# PentaFnord_LedBar_0_91r.net
KiCad netlist of a schematic drawn in EAGLE
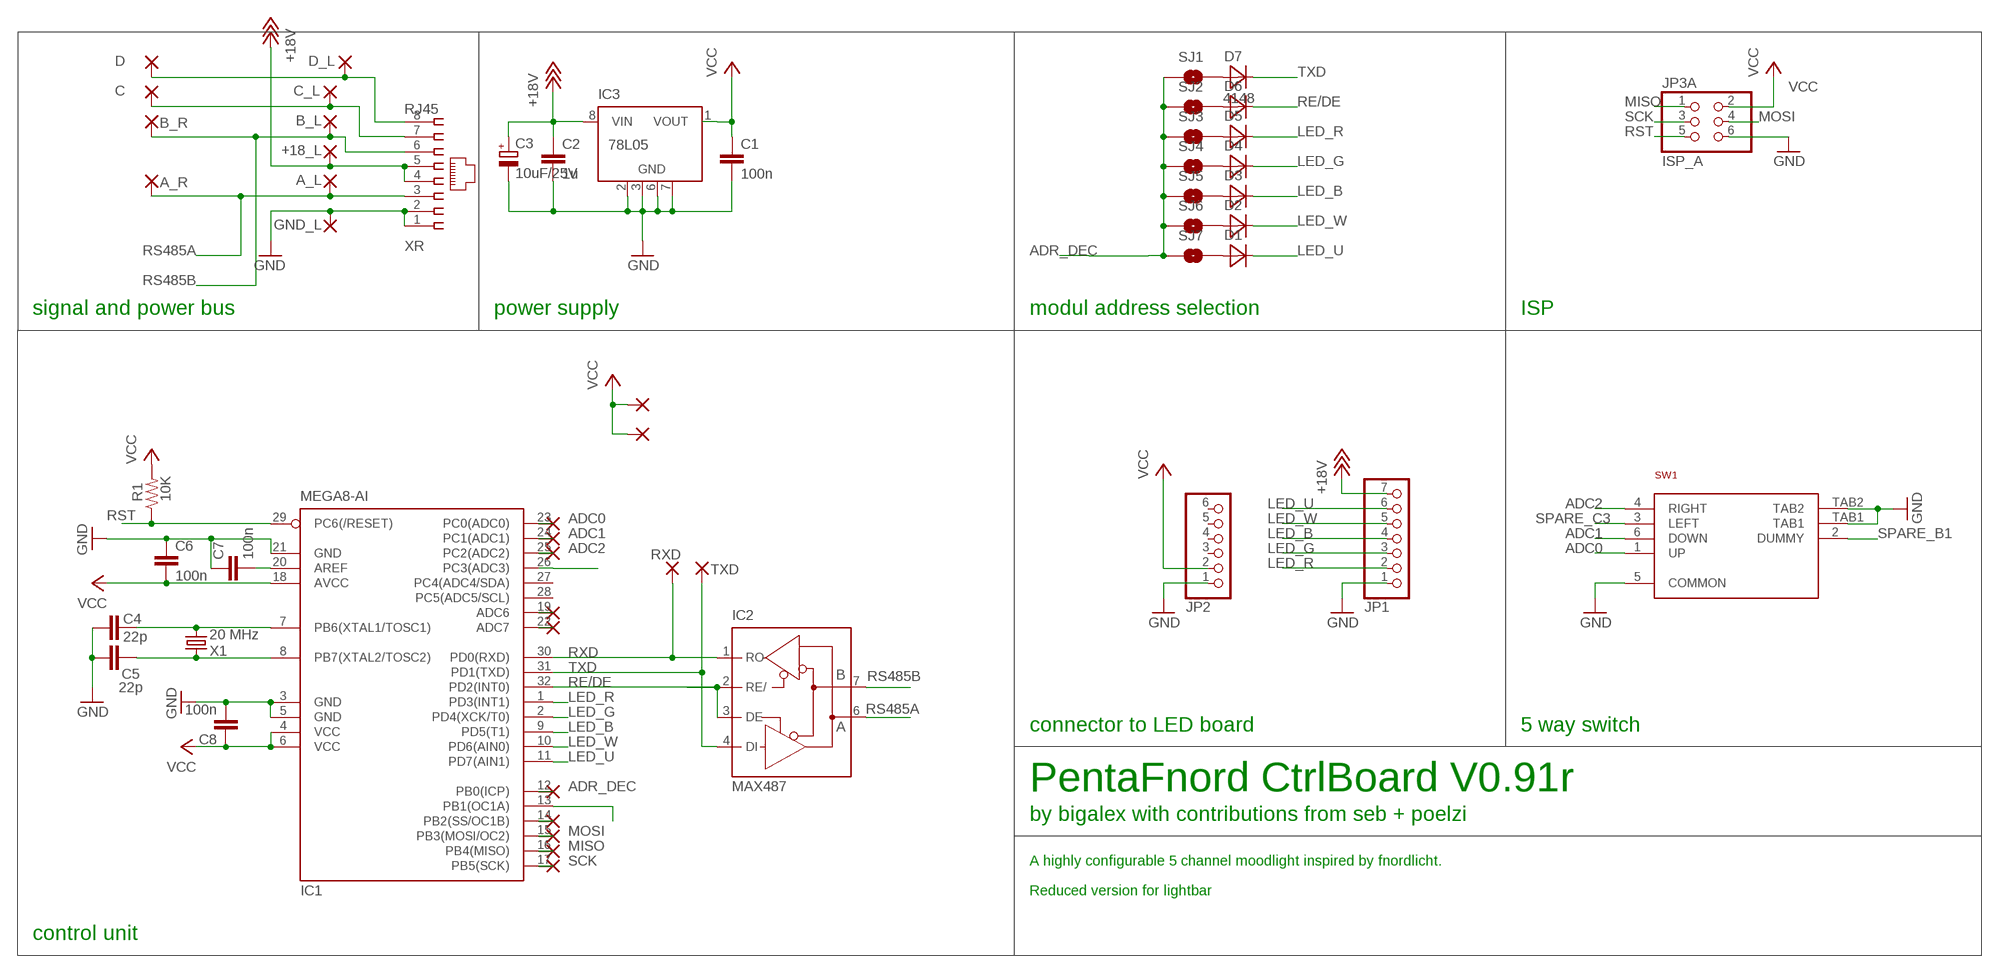
[diagram p0: schematic, sheet 1]
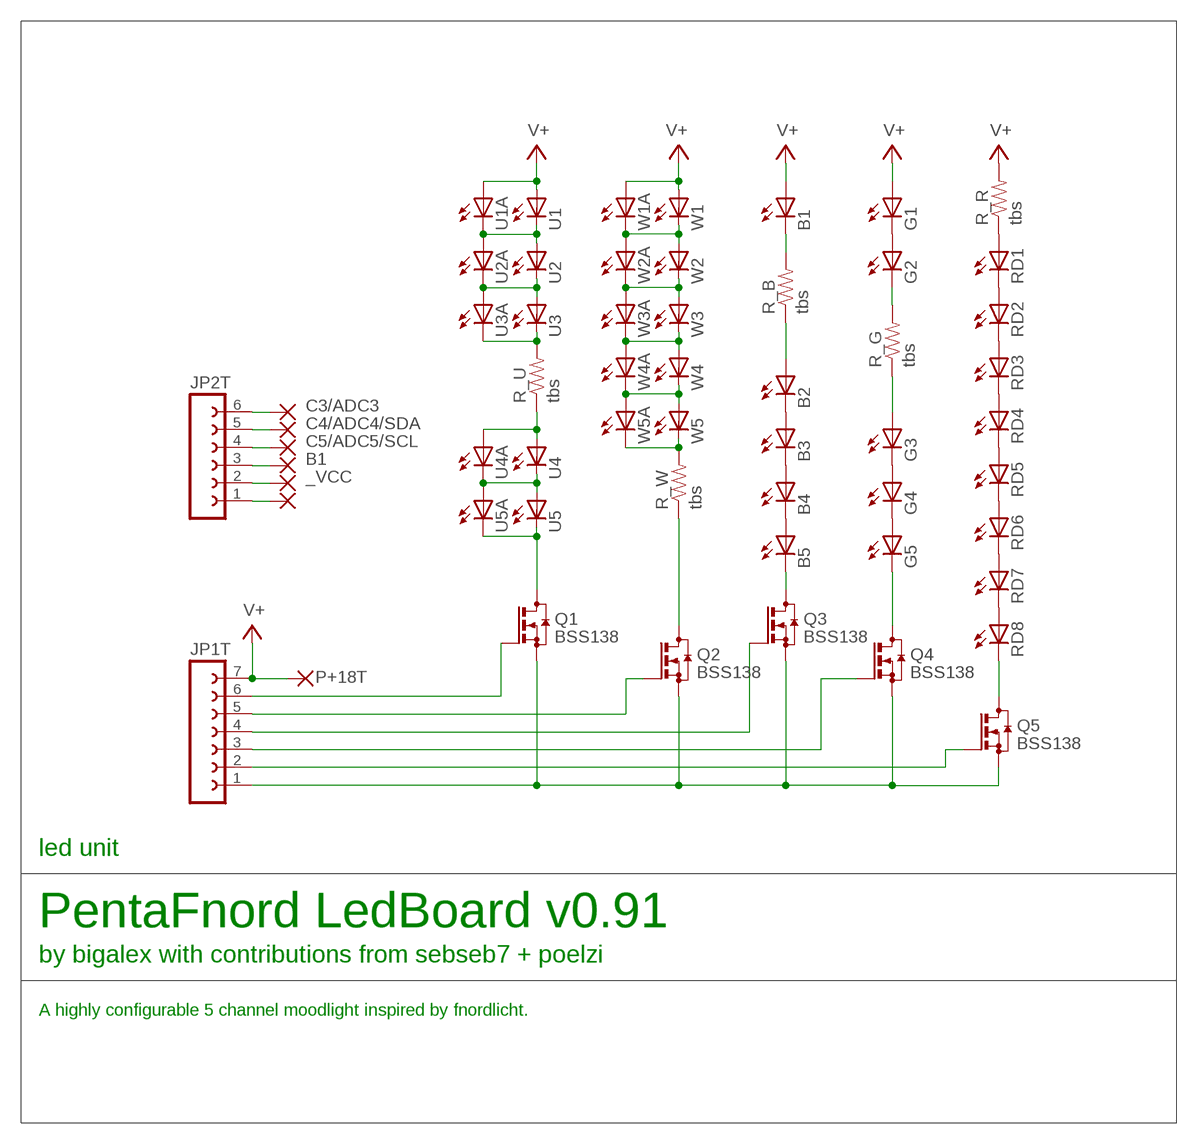
[diagram p1: schematic, sheet 2]

(export (version "E")
  (design (tool "Eeschema 10.0.6"))
  (components
    (comp (ref "B1")
      (value "LED5MM")
      (footprint "eagle-import:LED5MM")
      (libsource (lib "eagle-import") (part "LED5MM"))
    )
    (comp (ref "B2")
      (value "LED5MM")
      (footprint "eagle-import:LED5MM")
      (libsource (lib "eagle-import") (part "LED5MM"))
    )
    (comp (ref "B3")
      (value "LED5MM")
      (footprint "eagle-import:LED5MM")
      (libsource (lib "eagle-import") (part "LED5MM"))
    )
    (comp (ref "B4")
      (value "LED5MM")
      (footprint "eagle-import:LED5MM")
      (libsource (lib "eagle-import") (part "LED5MM"))
    )
    (comp (ref "B5")
      (value "LED5MM")
      (footprint "eagle-import:LED5MM")
      (libsource (lib "eagle-import") (part "LED5MM"))
    )
    (comp (ref "G1")
      (value "LED5MM")
      (footprint "eagle-import:LED5MM")
      (libsource (lib "eagle-import") (part "LED5MM"))
    )
    (comp (ref "G2")
      (value "LED5MM")
      (footprint "eagle-import:LED5MM")
      (libsource (lib "eagle-import") (part "LED5MM"))
    )
    (comp (ref "G3")
      (value "LED5MM")
      (footprint "eagle-import:LED5MM")
      (libsource (lib "eagle-import") (part "LED5MM"))
    )
    (comp (ref "G4")
      (value "LED5MM")
      (footprint "eagle-import:LED5MM")
      (libsource (lib "eagle-import") (part "LED5MM"))
    )
    (comp (ref "G5")
      (value "LED5MM")
      (footprint "eagle-import:LED5MM")
      (libsource (lib "eagle-import") (part "LED5MM"))
    )
    (comp (ref "JP1T")
      (value "FE07-1")
      (footprint "eagle-import:FE07")
      (libsource (lib "eagle-import") (part "FE07-1"))
    )
    (comp (ref "JP2T")
      (value "FE06-1")
      (footprint "eagle-import:FE06")
      (libsource (lib "eagle-import") (part "FE06-1"))
    )
    (comp (ref "P+5T")
      (value "WIREPAD2,54/0,8")
      (footprint "eagle-import:2,54_0,8")
      (libsource (lib "eagle-import") (part "WIREPAD2,54/0,8"))
    )
    (comp (ref "P+18T")
      (value "WIREPAD2,54/0,8")
      (footprint "eagle-import:2,54_0,8")
      (libsource (lib "eagle-import") (part "WIREPAD2,54/0,8"))
    )
    (comp (ref "PB1T")
      (value "WIREPAD2,54/0,8")
      (footprint "eagle-import:2,54_0,8")
      (libsource (lib "eagle-import") (part "WIREPAD2,54/0,8"))
    )
    (comp (ref "PC3T")
      (value "WIREPAD2,54/0,8")
      (footprint "eagle-import:2,54_0,8")
      (libsource (lib "eagle-import") (part "WIREPAD2,54/0,8"))
    )
    (comp (ref "PC4T")
      (value "WIREPAD2,54/0,8")
      (footprint "eagle-import:2,54_0,8")
      (libsource (lib "eagle-import") (part "WIREPAD2,54/0,8"))
    )
    (comp (ref "PC5T")
      (value "WIREPAD2,54/0,8")
      (footprint "eagle-import:2,54_0,8")
      (libsource (lib "eagle-import") (part "WIREPAD2,54/0,8"))
    )
    (comp (ref "PGNDT1")
      (value "WIREPAD2,54/0,8")
      (footprint "eagle-import:2,54_0,8")
      (libsource (lib "eagle-import") (part "WIREPAD2,54/0,8"))
    )
    (comp (ref "Q1")
      (value "BSS138")
      (footprint "eagle-import:SOT23")
      (libsource (lib "eagle-import") (part "BSS123"))
    )
    (comp (ref "Q2")
      (value "BSS138")
      (footprint "eagle-import:SOT23")
      (libsource (lib "eagle-import") (part "BSS123"))
    )
    (comp (ref "Q3")
      (value "BSS138")
      (footprint "eagle-import:SOT23")
      (libsource (lib "eagle-import") (part "BSS123"))
    )
    (comp (ref "Q4")
      (value "BSS138")
      (footprint "eagle-import:SOT23")
      (libsource (lib "eagle-import") (part "BSS123"))
    )
    (comp (ref "Q5")
      (value "BSS138")
      (footprint "eagle-import:SOT23")
      (libsource (lib "eagle-import") (part "BSS123"))
    )
    (comp (ref "RD1")
      (value "LED5MM")
      (footprint "eagle-import:LED5MM")
      (libsource (lib "eagle-import") (part "LED5MM"))
    )
    (comp (ref "RD2")
      (value "LED5MM")
      (footprint "eagle-import:LED5MM")
      (libsource (lib "eagle-import") (part "LED5MM"))
    )
    (comp (ref "RD3")
      (value "LED5MM")
      (footprint "eagle-import:LED5MM")
      (libsource (lib "eagle-import") (part "LED5MM"))
    )
    (comp (ref "RD4")
      (value "LED5MM")
      (footprint "eagle-import:LED5MM")
      (libsource (lib "eagle-import") (part "LED5MM"))
    )
    (comp (ref "RD5")
      (value "LED5MM")
      (footprint "eagle-import:LED5MM")
      (libsource (lib "eagle-import") (part "LED5MM"))
    )
    (comp (ref "RD6")
      (value "LED5MM")
      (footprint "eagle-import:LED5MM")
      (libsource (lib "eagle-import") (part "LED5MM"))
    )
    (comp (ref "RD7")
      (value "LED5MM")
      (footprint "eagle-import:LED5MM")
      (libsource (lib "eagle-import") (part "LED5MM"))
    )
    (comp (ref "RD8")
      (value "LED5MM")
      (footprint "eagle-import:LED5MM")
      (libsource (lib "eagle-import") (part "LED5MM"))
    )
    (comp (ref "R_B")
      (value "tbs")
      (footprint "eagle-import:1206")
      (libsource (lib "eagle-import") (part "RESISTOR1206"))
    )
    (comp (ref "R_G")
      (value "tbs")
      (footprint "eagle-import:1206")
      (libsource (lib "eagle-import") (part "RESISTOR1206"))
    )
    (comp (ref "R_R")
      (value "tbs")
      (footprint "eagle-import:1206")
      (libsource (lib "eagle-import") (part "RESISTOR1206"))
    )
    (comp (ref "R_U")
      (value "tbs")
      (footprint "eagle-import:1206")
      (libsource (lib "eagle-import") (part "RESISTOR1206"))
    )
    (comp (ref "R_W")
      (value "tbs")
      (footprint "eagle-import:1206")
      (libsource (lib "eagle-import") (part "RESISTOR1206"))
    )
    (comp (ref "U1")
      (value "NICHIA_NSSL157T-H3")
      (footprint "eagle-import:PLCC2")
      (libsource (lib "eagle-import") (part "LED_PLCC2"))
    )
    (comp (ref "U1A")
      (value "LED5MM")
      (footprint "eagle-import:LED5MM")
      (libsource (lib "eagle-import") (part "LED5MM"))
    )
    (comp (ref "U2")
      (value "NICHIA_NSSL157T-H3")
      (footprint "eagle-import:PLCC2")
      (libsource (lib "eagle-import") (part "LED_PLCC2"))
    )
    (comp (ref "U2A")
      (value "LED5MM")
      (footprint "eagle-import:LED5MM")
      (libsource (lib "eagle-import") (part "LED5MM"))
    )
    (comp (ref "U3")
      (value "NICHIA_NSSL157T-H3")
      (footprint "eagle-import:PLCC2")
      (libsource (lib "eagle-import") (part "LED_PLCC2"))
    )
    (comp (ref "U3A")
      (value "LED5MM")
      (footprint "eagle-import:LED5MM")
      (libsource (lib "eagle-import") (part "LED5MM"))
    )
    (comp (ref "U4")
      (value "NICHIA_NSSL157T-H3")
      (footprint "eagle-import:PLCC2")
      (libsource (lib "eagle-import") (part "LED_PLCC2"))
    )
    (comp (ref "U4A")
      (value "LED5MM")
      (footprint "eagle-import:LED5MM")
      (libsource (lib "eagle-import") (part "LED5MM"))
    )
    (comp (ref "U5")
      (value "NICHIA_NSSL157T-H3")
      (footprint "eagle-import:PLCC2")
      (libsource (lib "eagle-import") (part "LED_PLCC2"))
    )
    (comp (ref "U5A")
      (value "LED5MM")
      (footprint "eagle-import:LED5MM")
      (libsource (lib "eagle-import") (part "LED5MM"))
    )
    (comp (ref "W1")
      (value "NICHIA_NSSL157T-H3")
      (footprint "eagle-import:NICHIA_NSSL157T-H3")
      (libsource (lib "eagle-import") (part "NICHIA_NSSL157T-H3"))
    )
    (comp (ref "W1A")
      (value "LED5MM")
      (footprint "eagle-import:LED5MM")
      (libsource (lib "eagle-import") (part "LED5MM"))
    )
    (comp (ref "W2")
      (value "NICHIA_NSSL157T-H3")
      (footprint "eagle-import:NICHIA_NSSL157T-H3")
      (libsource (lib "eagle-import") (part "NICHIA_NSSL157T-H3"))
    )
    (comp (ref "W2A")
      (value "LED5MM")
      (footprint "eagle-import:LED5MM")
      (libsource (lib "eagle-import") (part "LED5MM"))
    )
    (comp (ref "W3")
      (value "NICHIA_NSSL157T-H3")
      (footprint "eagle-import:NICHIA_NSSL157T-H3")
      (libsource (lib "eagle-import") (part "NICHIA_NSSL157T-H3"))
    )
    (comp (ref "W3A")
      (value "LED5MM")
      (footprint "eagle-import:LED5MM")
      (libsource (lib "eagle-import") (part "LED5MM"))
    )
    (comp (ref "W4")
      (value "NICHIA_NSSL157T-H3")
      (footprint "eagle-import:NICHIA_NSSL157T-H3")
      (libsource (lib "eagle-import") (part "NICHIA_NSSL157T-H3"))
    )
    (comp (ref "W4A")
      (value "LED5MM")
      (footprint "eagle-import:LED5MM")
      (libsource (lib "eagle-import") (part "LED5MM"))
    )
    (comp (ref "W5")
      (value "NICHIA_NSSL157T-H3")
      (footprint "eagle-import:NICHIA_NSSL157T-H3")
      (libsource (lib "eagle-import") (part "NICHIA_NSSL157T-H3"))
    )
    (comp (ref "W5A")
      (value "LED5MM")
      (footprint "eagle-import:LED5MM")
      (libsource (lib "eagle-import") (part "LED5MM"))
    )
    (comp (ref "+18_L")
      (value "WIREPADSMD2,54-5,08")
      (footprint "eagle-import:SMD2,54-5,08")
      (libsource (lib "eagle-import") (part "WIREPADSMD2,54-5,08"))
    )
    (comp (ref "ADC6")
      (value "WIREPADSMD1,27-254")
      (footprint "eagle-import:SMD1,27-2,54")
      (libsource (lib "eagle-import") (part "WIREPADSMD1,27-254"))
    )
    (comp (ref "ADC7")
      (value "WIREPADSMD1,27-254")
      (footprint "eagle-import:SMD1,27-2,54")
      (libsource (lib "eagle-import") (part "WIREPADSMD1,27-254"))
    )
    (comp (ref "A_L")
      (value "WIREPADSMD2,54-5,08")
      (footprint "eagle-import:SMD2,54-5,08")
      (libsource (lib "eagle-import") (part "WIREPADSMD2,54-5,08"))
    )
    (comp (ref "A_R")
      (value "WIREPADSMD1,27-254")
      (footprint "eagle-import:SMD1,27-2,54")
      (libsource (lib "eagle-import") (part "WIREPADSMD1,27-254"))
    )
    (comp (ref "B_L")
      (value "WIREPADSMD2,54-5,08")
      (footprint "eagle-import:SMD2,54-5,08")
      (libsource (lib "eagle-import") (part "WIREPADSMD2,54-5,08"))
    )
    (comp (ref "B_R")
      (value "WIREPADSMD1,27-254")
      (footprint "eagle-import:SMD1,27-2,54")
      (libsource (lib "eagle-import") (part "WIREPADSMD1,27-254"))
    )
    (comp (ref "C")
      (value "WIREPADSMD1,27-254")
      (footprint "eagle-import:SMD1,27-2,54")
      (libsource (lib "eagle-import") (part "WIREPADSMD1,27-254"))
    )
    (comp (ref "C1")
      (value "100n")
      (footprint "eagle-import:0805")
      (libsource (lib "eagle-import") (part "CAP0805"))
    )
    (comp (ref "C2")
      (value "1u")
      (footprint "eagle-import:0805")
      (libsource (lib "eagle-import") (part "CAP0805"))
    )
    (comp (ref "C3")
      (value "10uF/25V")
      (footprint "eagle-import:SMC_D")
      (libsource (lib "eagle-import") (part "CPOL-EUSMCD"))
    )
    (comp (ref "C4")
      (value "22p")
      (footprint "eagle-import:0805")
      (libsource (lib "eagle-import") (part "CAP0805"))
    )
    (comp (ref "C5")
      (value "22p")
      (footprint "eagle-import:0805")
      (libsource (lib "eagle-import") (part "CAP0805"))
    )
    (comp (ref "C6")
      (value "100n")
      (footprint "eagle-import:0805")
      (libsource (lib "eagle-import") (part "CAP0805"))
    )
    (comp (ref "C7")
      (value "100n")
      (footprint "eagle-import:0805")
      (libsource (lib "eagle-import") (part "CAP0805"))
    )
    (comp (ref "C8")
      (value "100n")
      (footprint "eagle-import:0805")
      (libsource (lib "eagle-import") (part "CAP0805"))
    )
    (comp (ref "C_L")
      (value "WIREPADSMD2,54-5,08")
      (footprint "eagle-import:SMD2,54-5,08")
      (libsource (lib "eagle-import") (part "WIREPADSMD2,54-5,08"))
    )
    (comp (ref "D")
      (value "WIREPADSMD1,27-254")
      (footprint "eagle-import:SMD1,27-2,54")
      (libsource (lib "eagle-import") (part "WIREPADSMD1,27-254"))
    )
    (comp (ref "D1")
      (value "DIODE_0805")
      (footprint "eagle-import:DIODE_0805")
      (libsource (lib "eagle-import") (part "DIODE_0805"))
    )
    (comp (ref "D2")
      (value "DIODE_0805")
      (footprint "eagle-import:DIODE_0805")
      (libsource (lib "eagle-import") (part "DIODE_0805"))
    )
    (comp (ref "D3")
      (value "DIODE_0805")
      (footprint "eagle-import:DIODE_0805")
      (libsource (lib "eagle-import") (part "DIODE_0805"))
    )
    (comp (ref "D4")
      (value "DIODE_0805")
      (footprint "eagle-import:DIODE_0805")
      (libsource (lib "eagle-import") (part "DIODE_0805"))
    )
    (comp (ref "D5")
      (value "DIODE_0805")
      (footprint "eagle-import:DIODE_0805")
      (libsource (lib "eagle-import") (part "DIODE_0805"))
    )
    (comp (ref "D6")
      (value "DIODE_0805")
      (footprint "eagle-import:DIODE_0805")
      (libsource (lib "eagle-import") (part "DIODE_0805"))
    )
    (comp (ref "D7")
      (value "4148")
      (footprint "eagle-import:DIODE_0805")
      (libsource (lib "eagle-import") (part "DIODE_0805"))
    )
    (comp (ref "D_L")
      (value "WIREPADSMD2,54-5,08")
      (footprint "eagle-import:SMD2,54-5,08")
      (libsource (lib "eagle-import") (part "WIREPADSMD2,54-5,08"))
    )
    (comp (ref "GND_L")
      (value "WIREPADSMD2,54-5,08")
      (footprint "eagle-import:SMD2,54-5,08")
      (libsource (lib "eagle-import") (part "WIREPADSMD2,54-5,08"))
    )
    (comp (ref "IC1")
      (value "MEGA8-AI")
      (footprint "eagle-import:TQFP32-08")
      (fields (field (name "MPN") "ATMEGA8-16AU"))
      (libsource (lib "eagle-import") (part "MEGA8-AI"))
    )
    (comp (ref "IC2")
      (value "MAX487")
      (footprint "eagle-import:SO08")
      (fields (field (name "MF") "MAXIM"))
      (libsource (lib "eagle-import") (part "MAX487"))
    )
    (comp (ref "IC3")
      (value "78L05")
      (footprint "eagle-import:SO08")
      (libsource (lib "eagle-import") (part "78LSMD05"))
    )
    (comp (ref "JP1")
      (value "PINHD-1X07_2.54-SMD-REVERSE")
      (footprint "eagle-import:1X07SMD-REVERSE")
      (libsource (lib "eagle-import") (part "PINHD-1X07_2.54-SMD-REVERSE"))
    )
    (comp (ref "JP2")
      (value "PINHD-1X06_2.54-SMD")
      (footprint "eagle-import:1X06SMD")
      (libsource (lib "eagle-import") (part "PINHD-1X06_2.54-SMD"))
    )
    (comp (ref "JP3A")
      (value "ISP_A")
      (footprint "eagle-import:2X03SMD")
      (libsource (lib "eagle-import") (part "PINHD-2X03_2.54-SMD"))
    )
    (comp (ref "PAD3")
      (value "WIREPADSMD1,27-254")
      (footprint "eagle-import:SMD1,27-2,54")
      (libsource (lib "eagle-import") (part "WIREPADSMD1,27-254"))
    )
    (comp (ref "PAD4")
      (value "WIREPADSMD1,27-254")
      (footprint "eagle-import:SMD1,27-2,54")
      (libsource (lib "eagle-import") (part "WIREPADSMD1,27-254"))
    )
    (comp (ref "PB0")
      (value "WIREPADSMD1,27-254")
      (footprint "eagle-import:SMD1,27-2,54")
      (libsource (lib "eagle-import") (part "WIREPADSMD1,27-254"))
    )
    (comp (ref "PB2")
      (value "WIREPADSMD1,27-254")
      (footprint "eagle-import:SMD1,27-2,54")
      (libsource (lib "eagle-import") (part "WIREPADSMD1,27-254"))
    )
    (comp (ref "PB3")
      (value "WIREPADSMD1,27-254")
      (footprint "eagle-import:SMD1,27-2,54")
      (libsource (lib "eagle-import") (part "WIREPADSMD1,27-254"))
    )
    (comp (ref "PB4")
      (value "WIREPADSMD1,27-254")
      (footprint "eagle-import:SMD1,27-2,54")
      (libsource (lib "eagle-import") (part "WIREPADSMD1,27-254"))
    )
    (comp (ref "PB5")
      (value "WIREPADSMD1,27-254")
      (footprint "eagle-import:SMD1,27-2,54")
      (libsource (lib "eagle-import") (part "WIREPADSMD1,27-254"))
    )
    (comp (ref "PC0")
      (value "WIREPADSMD1,27-254")
      (footprint "eagle-import:SMD1,27-2,54")
      (libsource (lib "eagle-import") (part "WIREPADSMD1,27-254"))
    )
    (comp (ref "PC1")
      (value "WIREPADSMD1,27-254")
      (footprint "eagle-import:SMD1,27-2,54")
      (libsource (lib "eagle-import") (part "WIREPADSMD1,27-254"))
    )
    (comp (ref "PC2")
      (value "WIREPADSMD1,27-254")
      (footprint "eagle-import:SMD1,27-2,54")
      (libsource (lib "eagle-import") (part "WIREPADSMD1,27-254"))
    )
    (comp (ref "R1")
      (value "10K")
      (footprint "eagle-import:0805")
      (libsource (lib "eagle-import") (part "RESISTOR0805-RES"))
    )
    (comp (ref "RXD")
      (value "WIREPADSMD2,54-5,08")
      (footprint "eagle-import:SMD2,54-5,08")
      (libsource (lib "eagle-import") (part "WIREPADSMD2,54-5,08"))
    )
    (comp (ref "SJ1")
      (value "SOLDERJUMPERNO")
      (footprint "eagle-import:SJ_2S-NO")
      (libsource (lib "eagle-import") (part "SOLDERJUMPERNO"))
    )
    (comp (ref "SJ2")
      (value "SOLDERJUMPERNO")
      (footprint "eagle-import:SJ_2S-NO")
      (libsource (lib "eagle-import") (part "SOLDERJUMPERNO"))
    )
    (comp (ref "SJ3")
      (value "SOLDERJUMPERNO")
      (footprint "eagle-import:SJ_2S-NO")
      (libsource (lib "eagle-import") (part "SOLDERJUMPERNO"))
    )
    (comp (ref "SJ4")
      (value "SOLDERJUMPERNO")
      (footprint "eagle-import:SJ_2S-NO")
      (libsource (lib "eagle-import") (part "SOLDERJUMPERNO"))
    )
    (comp (ref "SJ5")
      (value "SOLDERJUMPERNO")
      (footprint "eagle-import:SJ_2S-NO")
      (libsource (lib "eagle-import") (part "SOLDERJUMPERNO"))
    )
    (comp (ref "SJ6")
      (value "SOLDERJUMPERNO")
      (footprint "eagle-import:SJ_2S-NO")
      (libsource (lib "eagle-import") (part "SOLDERJUMPERNO"))
    )
    (comp (ref "SJ7")
      (value "SOLDERJUMPERNO")
      (footprint "eagle-import:SJ_2S-NO")
      (libsource (lib "eagle-import") (part "SOLDERJUMPERNO"))
    )
    (comp (ref "SW1")
      (value "MCMT5-F-VADAPTED_FOOTPRINT")
      (footprint "eagle-import:MCMT5-F-V_ADAPTED")
      (libsource (lib "eagle-import") (part "MCMT5-F-VADAPTED_FOOTPRINT"))
    )
    (comp (ref "TXD")
      (value "WIREPADSMD2,54-5,08")
      (footprint "eagle-import:SMD2,54-5,08")
      (libsource (lib "eagle-import") (part "WIREPADSMD2,54-5,08"))
    )
    (comp (ref "X1")
      (value "20 MHz")
      (footprint "eagle-import:HC49UP-SMALL")
      (libsource (lib "eagle-import") (part "CRYSTALSMD-SMALLER"))
    )
    (comp (ref "XR")
      (value "RJ45")
      (footprint "eagle-import:85502-5008-SMALL")
      (libsource (lib "eagle-import") (part "RJ45-SMDRJ45-SMALL"))
    )
  )
  (nets
    (net (code "1") (name "+18V") (class "Default")
      (node (ref "+18_L") (pin "1") (pinfunction "P_1") (pintype "passive"))
      (node (ref "C2") (pin "1") (pinfunction "1_1") (pintype "passive"))
      (node (ref "C3") (pin "+") (pinfunction "+_+") (pintype "passive"))
      (node (ref "IC3") (pin "8") (pinfunction "VIN_8") (pintype "passive"))
      (node (ref "JP1") (pin "7") (pinfunction "7_7") (pintype "passive"))
      (node (ref "XR") (pin "4") (pinfunction "4_4") (pintype "passive"))
      (node (ref "XR") (pin "5") (pinfunction "5_5") (pintype "passive"))
    )
    (net (code "2") (name "ADC0") (class "Default")
      (node (ref "IC1") (pin "23") (pinfunction "PC0(ADC0)_23") (pintype "bidirectional"))
      (node (ref "PC0") (pin "1") (pinfunction "P_1") (pintype "passive"))
      (node (ref "SW1") (pin "1") (pinfunction "UP_1") (pintype "bidirectional"))
    )
    (net (code "3") (name "ADC1") (class "Default")
      (node (ref "IC1") (pin "24") (pinfunction "PC1(ADC1)_24") (pintype "bidirectional"))
      (node (ref "PC1") (pin "1") (pinfunction "P_1") (pintype "passive"))
      (node (ref "SW1") (pin "6") (pinfunction "DOWN_6") (pintype "bidirectional"))
    )
    (net (code "4") (name "ADC2") (class "Default")
      (node (ref "IC1") (pin "25") (pinfunction "PC2(ADC2)_25") (pintype "bidirectional"))
      (node (ref "PC2") (pin "1") (pinfunction "P_1") (pintype "passive"))
      (node (ref "SW1") (pin "4") (pinfunction "RIGHT_4") (pintype "bidirectional"))
    )
    (net (code "5") (name "ADR_DEC") (class "Default")
      (node (ref "IC1") (pin "12") (pinfunction "PB0(ICP)_12") (pintype "bidirectional"))
      (node (ref "PB0") (pin "1") (pinfunction "P_1") (pintype "passive"))
      (node (ref "SJ1") (pin "1") (pinfunction "1_1") (pintype "passive"))
      (node (ref "SJ2") (pin "1") (pinfunction "1_1") (pintype "passive"))
      (node (ref "SJ3") (pin "1") (pinfunction "1_1") (pintype "passive"))
      (node (ref "SJ4") (pin "1") (pinfunction "1_1") (pintype "passive"))
      (node (ref "SJ5") (pin "1") (pinfunction "1_1") (pintype "passive"))
      (node (ref "SJ6") (pin "1") (pinfunction "1_1") (pintype "passive"))
      (node (ref "SJ7") (pin "1") (pinfunction "1_1") (pintype "passive"))
    )
    (net (code "6") (name "B1") (class "Default")
      (node (ref "JP2T") (pin "3") (pinfunction "3_3") (pintype "passive"))
      (node (ref "PB1T") (pin "1") (pinfunction "P_1") (pintype "passive"))
    )
    (net (code "7") (name "C3{slash}ADC3") (class "Default")
      (node (ref "JP2T") (pin "6") (pinfunction "6_6") (pintype "passive"))
      (node (ref "PC3T") (pin "1") (pinfunction "P_1") (pintype "passive"))
    )
    (net (code "8") (name "C4{slash}ADC4{slash}SDA") (class "Default")
      (node (ref "JP2T") (pin "5") (pinfunction "5_5") (pintype "passive"))
      (node (ref "PC4T") (pin "1") (pinfunction "P_1") (pintype "passive"))
    )
    (net (code "9") (name "C5{slash}ADC5{slash}SCL") (class "Default")
      (node (ref "JP2T") (pin "4") (pinfunction "4_4") (pintype "passive"))
      (node (ref "PC5T") (pin "1") (pinfunction "P_1") (pintype "passive"))
    )
    (net (code "10") (name "GND") (class "Default")
      (node (ref "C1") (pin "2") (pinfunction "2_2") (pintype "passive"))
      (node (ref "C2") (pin "2") (pinfunction "2_2") (pintype "passive"))
      (node (ref "C3") (pin "-") (pinfunction "-_-") (pintype "passive"))
      (node (ref "C4") (pin "1") (pinfunction "1_1") (pintype "passive"))
      (node (ref "C5") (pin "1") (pinfunction "1_1") (pintype "passive"))
      (node (ref "C6") (pin "1") (pinfunction "1_1") (pintype "passive"))
      (node (ref "C7") (pin "1") (pinfunction "1_1") (pintype "passive"))
      (node (ref "C8") (pin "2") (pinfunction "2_2") (pintype "passive"))
      (node (ref "GND_L") (pin "1") (pinfunction "P_1") (pintype "passive"))
      (node (ref "IC1") (pin "21") (pinfunction "GND_21") (pintype "power_in"))
      (node (ref "IC1") (pin "3") (pinfunction "GND_3") (pintype "power_in"))
      (node (ref "IC1") (pin "5") (pinfunction "GND_5") (pintype "power_in"))
      (node (ref "IC3") (pin "2") (pinfunction "GND_2") (pintype "power_in"))
      (node (ref "IC3") (pin "3") (pinfunction "GND_3") (pintype "power_in"))
      (node (ref "IC3") (pin "6") (pinfunction "GND_6") (pintype "power_in"))
      (node (ref "IC3") (pin "7") (pinfunction "GND_7") (pintype "power_in"))
      (node (ref "JP1") (pin "1") (pinfunction "1_1") (pintype "passive"))
      (node (ref "JP2") (pin "1") (pinfunction "1_1") (pintype "passive"))
      (node (ref "JP3A") (pin "6") (pinfunction "6_6") (pintype "passive"))
      (node (ref "SW1") (pin "5") (pinfunction "COMMON_5") (pintype "bidirectional"))
      (node (ref "SW1") (pin "TAB1") (pinfunction "TAB1_TAB1") (pintype "bidirectional"))
      (node (ref "SW1") (pin "TAB2") (pinfunction "TAB2_TAB2") (pintype "bidirectional"))
      (node (ref "XR") (pin "1") (pinfunction "1_1") (pintype "passive"))
      (node (ref "XR") (pin "2") (pinfunction "2_2") (pintype "passive"))
    )
    (net (code "11") (name "GND_T") (class "Default")
      (node (ref "JP1T") (pin "1") (pinfunction "1_1") (pintype "passive"))
      (node (ref "JP2T") (pin "1") (pinfunction "1_1") (pintype "passive"))
      (node (ref "PGNDT1") (pin "1") (pinfunction "P_1") (pintype "passive"))
      (node (ref "Q1") (pin "2") (pinfunction "S_2") (pintype "passive"))
      (node (ref "Q2") (pin "2") (pinfunction "S_2") (pintype "passive"))
      (node (ref "Q3") (pin "2") (pinfunction "S_2") (pintype "passive"))
      (node (ref "Q4") (pin "2") (pinfunction "S_2") (pintype "passive"))
      (node (ref "Q5") (pin "2") (pinfunction "S_2") (pintype "passive"))
    )
    (net (code "12") (name "LED_B") (class "Default")
      (node (ref "D3") (pin "1") (pinfunction "C_1") (pintype "passive"))
      (node (ref "IC1") (pin "9") (pinfunction "PD5(T1)_9") (pintype "bidirectional"))
      (node (ref "JP1") (pin "4") (pinfunction "4_4") (pintype "passive"))
    )
    (net (code "13") (name "LED_G") (class "Default")
      (node (ref "D4") (pin "1") (pinfunction "C_1") (pintype "passive"))
      (node (ref "IC1") (pin "2") (pinfunction "PD4(XCK/T0)_2") (pintype "bidirectional"))
      (node (ref "JP1") (pin "3") (pinfunction "3_3") (pintype "passive"))
    )
    (net (code "14") (name "LED_R") (class "Default")
      (node (ref "D5") (pin "1") (pinfunction "C_1") (pintype "passive"))
      (node (ref "IC1") (pin "1") (pinfunction "PD3(INT1)_1") (pintype "bidirectional"))
      (node (ref "JP1") (pin "2") (pinfunction "2_2") (pintype "passive"))
    )
    (net (code "15") (name "LED_U") (class "Default")
      (node (ref "D1") (pin "1") (pinfunction "C_1") (pintype "passive"))
      (node (ref "IC1") (pin "11") (pinfunction "PD7(AIN1)_11") (pintype "bidirectional"))
      (node (ref "JP1") (pin "6") (pinfunction "6_6") (pintype "passive"))
    )
    (net (code "16") (name "LED_W") (class "Default")
      (node (ref "D2") (pin "1") (pinfunction "C_1") (pintype "passive"))
      (node (ref "IC1") (pin "10") (pinfunction "PD6(AIN0)_10") (pintype "bidirectional"))
      (node (ref "JP1") (pin "5") (pinfunction "5_5") (pintype "passive"))
    )
    (net (code "17") (name "MISO") (class "Default")
      (node (ref "IC1") (pin "16") (pinfunction "PB4(MISO)_16") (pintype "bidirectional"))
      (node (ref "JP3A") (pin "1") (pinfunction "1_1") (pintype "passive"))
      (node (ref "PB4") (pin "1") (pinfunction "P_1") (pintype "passive"))
    )
    (net (code "18") (name "MOSI") (class "Default")
      (node (ref "IC1") (pin "15") (pinfunction "PB3(MOSI/OC2)_15") (pintype "bidirectional"))
      (node (ref "JP3A") (pin "4") (pinfunction "4_4") (pintype "passive"))
      (node (ref "PB3") (pin "1") (pinfunction "P_1") (pintype "passive"))
    )
    (net (code "19") (name "Net-(ADC6-P)") (class "Default")
      (node (ref "ADC6") (pin "1") (pinfunction "P_1") (pintype "passive"))
      (node (ref "IC1") (pin "19") (pinfunction "ADC6_19") (pintype "bidirectional"))
    )
    (net (code "20") (name "Net-(ADC7-P)") (class "Default")
      (node (ref "ADC7") (pin "1") (pinfunction "P_1") (pintype "passive"))
      (node (ref "IC1") (pin "22") (pinfunction "ADC7_22") (pintype "bidirectional"))
    )
    (net (code "21") (name "Net-(B1-C)") (class "Default")
      (node (ref "B1") (pin "K") (pinfunction "C_K") (pintype "passive"))
      (node (ref "R_B") (pin "2") (pinfunction "2_2") (pintype "passive"))
    )
    (net (code "22") (name "Net-(B2-C)") (class "Default")
      (node (ref "B2") (pin "K") (pinfunction "C_K") (pintype "passive"))
      (node (ref "B3") (pin "A") (pinfunction "A_A") (pintype "passive"))
    )
    (net (code "23") (name "Net-(B2-PadA)") (class "Default")
      (node (ref "B2") (pin "A") (pinfunction "A_A") (pintype "passive"))
      (node (ref "R_B") (pin "1") (pinfunction "1_1") (pintype "passive"))
    )
    (net (code "24") (name "Net-(B3-C)") (class "Default")
      (node (ref "B3") (pin "K") (pinfunction "C_K") (pintype "passive"))
      (node (ref "B4") (pin "A") (pinfunction "A_A") (pintype "passive"))
    )
    (net (code "25") (name "Net-(B4-C)") (class "Default")
      (node (ref "B4") (pin "K") (pinfunction "C_K") (pintype "passive"))
      (node (ref "B5") (pin "A") (pinfunction "A_A") (pintype "passive"))
    )
    (net (code "26") (name "Net-(B5-C)") (class "Default")
      (node (ref "B5") (pin "K") (pinfunction "C_K") (pintype "passive"))
      (node (ref "Q3") (pin "3") (pinfunction "D_3") (pintype "passive"))
    )
    (net (code "27") (name "Net-(C-P)") (class "Default")
      (node (ref "C") (pin "1") (pinfunction "P_1") (pintype "passive"))
      (node (ref "C_L") (pin "1") (pinfunction "P_1") (pintype "passive"))
      (node (ref "XR") (pin "7") (pinfunction "7_7") (pintype "passive"))
    )
    (net (code "28") (name "Net-(D-P)") (class "Default")
      (node (ref "D") (pin "1") (pinfunction "P_1") (pintype "passive"))
      (node (ref "D_L") (pin "1") (pinfunction "P_1") (pintype "passive"))
      (node (ref "XR") (pin "8") (pinfunction "8_8") (pintype "passive"))
    )
    (net (code "29") (name "Net-(D1-A)") (class "Default")
      (node (ref "D1") (pin "2") (pinfunction "A_2") (pintype "passive"))
      (node (ref "SJ7") (pin "2") (pinfunction "2_2") (pintype "passive"))
    )
    (net (code "30") (name "Net-(D2-A)") (class "Default")
      (node (ref "D2") (pin "2") (pinfunction "A_2") (pintype "passive"))
      (node (ref "SJ6") (pin "2") (pinfunction "2_2") (pintype "passive"))
    )
    (net (code "31") (name "Net-(D3-A)") (class "Default")
      (node (ref "D3") (pin "2") (pinfunction "A_2") (pintype "passive"))
      (node (ref "SJ5") (pin "2") (pinfunction "2_2") (pintype "passive"))
    )
    (net (code "32") (name "Net-(D4-A)") (class "Default")
      (node (ref "D4") (pin "2") (pinfunction "A_2") (pintype "passive"))
      (node (ref "SJ4") (pin "2") (pinfunction "2_2") (pintype "passive"))
    )
    (net (code "33") (name "Net-(D5-A)") (class "Default")
      (node (ref "D5") (pin "2") (pinfunction "A_2") (pintype "passive"))
      (node (ref "SJ3") (pin "2") (pinfunction "2_2") (pintype "passive"))
    )
    (net (code "34") (name "Net-(D6-A)") (class "Default")
      (node (ref "D6") (pin "2") (pinfunction "A_2") (pintype "passive"))
      (node (ref "SJ2") (pin "2") (pinfunction "2_2") (pintype "passive"))
    )
    (net (code "35") (name "Net-(D7-A)") (class "Default")
      (node (ref "D7") (pin "2") (pinfunction "A_2") (pintype "passive"))
      (node (ref "SJ1") (pin "2") (pinfunction "2_2") (pintype "passive"))
    )
    (net (code "36") (name "Net-(G1-C)") (class "Default")
      (node (ref "G1") (pin "K") (pinfunction "C_K") (pintype "passive"))
      (node (ref "G2") (pin "A") (pinfunction "A_A") (pintype "passive"))
    )
    (net (code "37") (name "Net-(G2-C)") (class "Default")
      (node (ref "G2") (pin "K") (pinfunction "C_K") (pintype "passive"))
      (node (ref "R_G") (pin "2") (pinfunction "2_2") (pintype "passive"))
    )
    (net (code "38") (name "Net-(G3-C)") (class "Default")
      (node (ref "G3") (pin "K") (pinfunction "C_K") (pintype "passive"))
      (node (ref "G4") (pin "A") (pinfunction "A_A") (pintype "passive"))
    )
    (net (code "39") (name "Net-(G3-PadA)") (class "Default")
      (node (ref "G3") (pin "A") (pinfunction "A_A") (pintype "passive"))
      (node (ref "R_G") (pin "1") (pinfunction "1_1") (pintype "passive"))
    )
    (net (code "40") (name "Net-(G4-C)") (class "Default")
      (node (ref "G4") (pin "K") (pinfunction "C_K") (pintype "passive"))
      (node (ref "G5") (pin "A") (pinfunction "A_A") (pintype "passive"))
    )
    (net (code "41") (name "Net-(G5-C)") (class "Default")
      (node (ref "G5") (pin "K") (pinfunction "C_K") (pintype "passive"))
      (node (ref "Q4") (pin "3") (pinfunction "D_3") (pintype "passive"))
    )
    (net (code "42") (name "Net-(IC1-AREF)") (class "Default")
      (node (ref "C7") (pin "2") (pinfunction "2_2") (pintype "passive"))
      (node (ref "IC1") (pin "20") (pinfunction "AREF_20") (pintype "passive"))
    )
    (net (code "43") (name "Net-(IC1-PB2(SS{slash}OC1B))") (class "Default")
      (node (ref "IC1") (pin "14") (pinfunction "PB2(SS/OC1B)_14") (pintype "bidirectional"))
      (node (ref "PB2") (pin "1") (pinfunction "P_1") (pintype "passive"))
    )
    (net (code "44") (name "Net-(IC1-PB6(XTAL1{slash}TOSC1))") (class "Default")
      (node (ref "C4") (pin "2") (pinfunction "2_2") (pintype "passive"))
      (node (ref "IC1") (pin "7") (pinfunction "PB6(XTAL1/TOSC1)_7") (pintype "bidirectional"))
      (node (ref "X1") (pin "1") (pinfunction "1_1") (pintype "passive"))
    )
    (net (code "45") (name "Net-(IC1-PB7(XTAL2{slash}TOSC2))") (class "Default")
      (node (ref "C5") (pin "2") (pinfunction "2_2") (pintype "passive"))
      (node (ref "IC1") (pin "8") (pinfunction "PB7(XTAL2/TOSC2)_8") (pintype "bidirectional"))
      (node (ref "X1") (pin "2") (pinfunction "2_2") (pintype "passive"))
    )
    (net (code "46") (name "Net-(Q1-D)") (class "Default")
      (node (ref "Q1") (pin "3") (pinfunction "D_3") (pintype "passive"))
      (node (ref "U5") (pin "P$1") (pinfunction "C_P$1") (pintype "passive"))
      (node (ref "U5A") (pin "K") (pinfunction "C_K") (pintype "passive"))
    )
    (net (code "47") (name "Net-(Q1-G)") (class "Default")
      (node (ref "JP1T") (pin "6") (pinfunction "6_6") (pintype "passive"))
      (node (ref "Q1") (pin "1") (pinfunction "G_1") (pintype "passive"))
    )
    (net (code "48") (name "Net-(Q2-D)") (class "Default")
      (node (ref "Q2") (pin "3") (pinfunction "D_3") (pintype "passive"))
      (node (ref "R_W") (pin "1") (pinfunction "1_1") (pintype "passive"))
    )
    (net (code "49") (name "Net-(Q2-G)") (class "Default")
      (node (ref "JP1T") (pin "5") (pinfunction "5_5") (pintype "passive"))
      (node (ref "Q2") (pin "1") (pinfunction "G_1") (pintype "passive"))
    )
    (net (code "50") (name "Net-(Q3-G)") (class "Default")
      (node (ref "JP1T") (pin "4") (pinfunction "4_4") (pintype "passive"))
      (node (ref "Q3") (pin "1") (pinfunction "G_1") (pintype "passive"))
    )
    (net (code "51") (name "Net-(Q4-G)") (class "Default")
      (node (ref "JP1T") (pin "3") (pinfunction "3_3") (pintype "passive"))
      (node (ref "Q4") (pin "1") (pinfunction "G_1") (pintype "passive"))
    )
    (net (code "52") (name "Net-(Q5-D)") (class "Default")
      (node (ref "Q5") (pin "3") (pinfunction "D_3") (pintype "passive"))
      (node (ref "RD8") (pin "K") (pinfunction "C_K") (pintype "passive"))
    )
    (net (code "53") (name "Net-(Q5-G)") (class "Default")
      (node (ref "JP1T") (pin "2") (pinfunction "2_2") (pintype "passive"))
      (node (ref "Q5") (pin "1") (pinfunction "G_1") (pintype "passive"))
    )
    (net (code "54") (name "Net-(RD1-C)") (class "Default")
      (node (ref "RD1") (pin "K") (pinfunction "C_K") (pintype "passive"))
      (node (ref "RD2") (pin "A") (pinfunction "A_A") (pintype "passive"))
    )
    (net (code "55") (name "Net-(RD1-PadA)") (class "Default")
      (node (ref "RD1") (pin "A") (pinfunction "A_A") (pintype "passive"))
      (node (ref "R_R") (pin "1") (pinfunction "1_1") (pintype "passive"))
    )
    (net (code "56") (name "Net-(RD2-C)") (class "Default")
      (node (ref "RD2") (pin "K") (pinfunction "C_K") (pintype "passive"))
      (node (ref "RD3") (pin "A") (pinfunction "A_A") (pintype "passive"))
    )
    (net (code "57") (name "Net-(RD3-C)") (class "Default")
      (node (ref "RD3") (pin "K") (pinfunction "C_K") (pintype "passive"))
      (node (ref "RD4") (pin "A") (pinfunction "A_A") (pintype "passive"))
    )
    (net (code "58") (name "Net-(RD4-C)") (class "Default")
      (node (ref "RD4") (pin "K") (pinfunction "C_K") (pintype "passive"))
      (node (ref "RD5") (pin "A") (pinfunction "A_A") (pintype "passive"))
    )
    (net (code "59") (name "Net-(RD5-C)") (class "Default")
      (node (ref "RD5") (pin "K") (pinfunction "C_K") (pintype "passive"))
      (node (ref "RD6") (pin "A") (pinfunction "A_A") (pintype "passive"))
    )
    (net (code "60") (name "Net-(RD6-C)") (class "Default")
      (node (ref "RD6") (pin "K") (pinfunction "C_K") (pintype "passive"))
      (node (ref "RD7") (pin "A") (pinfunction "A_A") (pintype "passive"))
    )
    (net (code "61") (name "Net-(RD7-C)") (class "Default")
      (node (ref "RD7") (pin "K") (pinfunction "C_K") (pintype "passive"))
      (node (ref "RD8") (pin "A") (pinfunction "A_A") (pintype "passive"))
    )
    (net (code "62") (name "Net-(U1-C)") (class "Default")
      (node (ref "U1") (pin "P$1") (pinfunction "C_P$1") (pintype "passive"))
      (node (ref "U1A") (pin "K") (pinfunction "C_K") (pintype "passive"))
      (node (ref "U2") (pin "P$2") (pinfunction "A_P$2") (pintype "passive"))
      (node (ref "U2A") (pin "A") (pinfunction "A_A") (pintype "passive"))
    )
    (net (code "63") (name "Net-(U2-C)") (class "Default")
      (node (ref "U2") (pin "P$1") (pinfunction "C_P$1") (pintype "passive"))
      (node (ref "U2A") (pin "K") (pinfunction "C_K") (pintype "passive"))
      (node (ref "U3") (pin "P$2") (pinfunction "A_P$2") (pintype "passive"))
      (node (ref "U3A") (pin "A") (pinfunction "A_A") (pintype "passive"))
    )
    (net (code "64") (name "Net-(U3-C)") (class "Default")
      (node (ref "R_U") (pin "2") (pinfunction "2_2") (pintype "passive"))
      (node (ref "U3") (pin "P$1") (pinfunction "C_P$1") (pintype "passive"))
      (node (ref "U3A") (pin "K") (pinfunction "C_K") (pintype "passive"))
    )
    (net (code "65") (name "Net-(U4-A)") (class "Default")
      (node (ref "R_U") (pin "1") (pinfunction "1_1") (pintype "passive"))
      (node (ref "U4") (pin "P$2") (pinfunction "A_P$2") (pintype "passive"))
      (node (ref "U4A") (pin "A") (pinfunction "A_A") (pintype "passive"))
    )
    (net (code "66") (name "Net-(U4-C)") (class "Default")
      (node (ref "U4") (pin "P$1") (pinfunction "C_P$1") (pintype "passive"))
      (node (ref "U4A") (pin "K") (pinfunction "C_K") (pintype "passive"))
      (node (ref "U5") (pin "P$2") (pinfunction "A_P$2") (pintype "passive"))
      (node (ref "U5A") (pin "A") (pinfunction "A_A") (pintype "passive"))
    )
    (net (code "67") (name "Net-(W1-C)") (class "Default")
      (node (ref "W1") (pin "K@1") (pinfunction "C_K@1") (pintype "passive"))
      (node (ref "W1A") (pin "K") (pinfunction "C_K") (pintype "passive"))
      (node (ref "W2") (pin "A@2") (pinfunction "A_A@2") (pintype "passive"))
      (node (ref "W2A") (pin "A") (pinfunction "A_A") (pintype "passive"))
    )
    (net (code "68") (name "Net-(W2-C)") (class "Default")
      (node (ref "W2") (pin "K@1") (pinfunction "C_K@1") (pintype "passive"))
      (node (ref "W2A") (pin "K") (pinfunction "C_K") (pintype "passive"))
      (node (ref "W3") (pin "A@2") (pinfunction "A_A@2") (pintype "passive"))
      (node (ref "W3A") (pin "A") (pinfunction "A_A") (pintype "passive"))
    )
    (net (code "69") (name "Net-(W3-C)") (class "Default")
      (node (ref "W3") (pin "K@1") (pinfunction "C_K@1") (pintype "passive"))
      (node (ref "W3A") (pin "K") (pinfunction "C_K") (pintype "passive"))
      (node (ref "W4") (pin "A@2") (pinfunction "A_A@2") (pintype "passive"))
      (node (ref "W4A") (pin "A") (pinfunction "A_A") (pintype "passive"))
    )
    (net (code "70") (name "Net-(W4-C)") (class "Default")
      (node (ref "W4") (pin "K@1") (pinfunction "C_K@1") (pintype "passive"))
      (node (ref "W4A") (pin "K") (pinfunction "C_K") (pintype "passive"))
      (node (ref "W5") (pin "A@2") (pinfunction "A_A@2") (pintype "passive"))
      (node (ref "W5A") (pin "A") (pinfunction "A_A") (pintype "passive"))
    )
    (net (code "71") (name "Net-(W5-C)") (class "Default")
      (node (ref "R_W") (pin "2") (pinfunction "2_2") (pintype "passive"))
      (node (ref "W5") (pin "K@1") (pinfunction "C_K@1") (pintype "passive"))
      (node (ref "W5A") (pin "K") (pinfunction "C_K") (pintype "passive"))
    )
    (net (code "72") (name "RE{slash}DE") (class "Default")
      (node (ref "D6") (pin "1") (pinfunction "C_1") (pintype "passive"))
      (node (ref "IC1") (pin "32") (pinfunction "PD2(INT0)_32") (pintype "bidirectional"))
      (node (ref "IC2") (pin "2") (pinfunction "RE/_2") (pintype "input"))
      (node (ref "IC2") (pin "3") (pinfunction "DE_3") (pintype "input"))
    )
    (net (code "73") (name "RS485A") (class "Default")
      (node (ref "A_L") (pin "1") (pinfunction "P_1") (pintype "passive"))
      (node (ref "A_R") (pin "1") (pinfunction "P_1") (pintype "passive"))
      (node (ref "IC2") (pin "6") (pinfunction "A_6") (pintype "passive"))
      (node (ref "XR") (pin "3") (pinfunction "3_3") (pintype "passive"))
    )
    (net (code "74") (name "RS485B") (class "Default")
      (node (ref "B_L") (pin "1") (pinfunction "P_1") (pintype "passive"))
      (node (ref "B_R") (pin "1") (pinfunction "P_1") (pintype "passive"))
      (node (ref "IC2") (pin "7") (pinfunction "B_7") (pintype "passive"))
      (node (ref "XR") (pin "6") (pinfunction "6_6") (pintype "passive"))
    )
    (net (code "75") (name "RST") (class "Default")
      (node (ref "IC1") (pin "29") (pinfunction "PC6(/RESET)_29") (pintype "bidirectional"))
      (node (ref "JP3A") (pin "5") (pinfunction "5_5") (pintype "passive"))
      (node (ref "R1") (pin "1") (pinfunction "1_1") (pintype "passive"))
    )
    (net (code "76") (name "RXD") (class "Default")
      (node (ref "IC1") (pin "30") (pinfunction "PD0(RXD)_30") (pintype "bidirectional"))
      (node (ref "IC2") (pin "1") (pinfunction "RO_1") (pintype "output"))
      (node (ref "RXD") (pin "1") (pinfunction "P_1") (pintype "passive"))
    )
    (net (code "77") (name "SCK") (class "Default")
      (node (ref "IC1") (pin "17") (pinfunction "PB5(SCK)_17") (pintype "bidirectional"))
      (node (ref "JP3A") (pin "3") (pinfunction "3_3") (pintype "passive"))
      (node (ref "PB5") (pin "1") (pinfunction "P_1") (pintype "passive"))
    )
    (net (code "78") (name "SPARE_B1") (class "Default")
      (node (ref "IC1") (pin "13") (pinfunction "PB1(OC1A)_13") (pintype "bidirectional"))
      (node (ref "SW1") (pin "2") (pinfunction "DUMMY_2") (pintype "bidirectional"))
    )
    (net (code "79") (name "SPARE_C3") (class "Default")
      (node (ref "IC1") (pin "26") (pinfunction "PC3(ADC3)_26") (pintype "bidirectional"))
      (node (ref "SW1") (pin "3") (pinfunction "LEFT_3") (pintype "bidirectional"))
    )
    (net (code "80") (name "TXD") (class "Default")
      (node (ref "D7") (pin "1") (pinfunction "C_1") (pintype "passive"))
      (node (ref "IC1") (pin "31") (pinfunction "PD1(TXD)_31") (pintype "bidirectional"))
      (node (ref "IC2") (pin "4") (pinfunction "DI_4") (pintype "input"))
      (node (ref "TXD") (pin "1") (pinfunction "P_1") (pintype "passive"))
    )
    (net (code "81") (name "V+") (class "Default")
      (node (ref "B1") (pin "A") (pinfunction "A_A") (pintype "passive"))
      (node (ref "G1") (pin "A") (pinfunction "A_A") (pintype "passive"))
      (node (ref "JP1T") (pin "7") (pinfunction "7_7") (pintype "passive"))
      (node (ref "P+18T") (pin "1") (pinfunction "P_1") (pintype "passive"))
      (node (ref "R_R") (pin "2") (pinfunction "2_2") (pintype "passive"))
      (node (ref "U1") (pin "P$2") (pinfunction "A_P$2") (pintype "passive"))
      (node (ref "U1A") (pin "A") (pinfunction "A_A") (pintype "passive"))
      (node (ref "W1") (pin "A@2") (pinfunction "A_A@2") (pintype "passive"))
      (node (ref "W1A") (pin "A") (pinfunction "A_A") (pintype "passive"))
    )
    (net (code "82") (name "VCC") (class "Default")
      (node (ref "C1") (pin "1") (pinfunction "1_1") (pintype "passive"))
      (node (ref "C6") (pin "2") (pinfunction "2_2") (pintype "passive"))
      (node (ref "C8") (pin "1") (pinfunction "1_1") (pintype "passive"))
      (node (ref "IC1") (pin "18") (pinfunction "AVCC_18") (pintype "power_in"))
      (node (ref "IC1") (pin "4") (pinfunction "VCC_4") (pintype "power_in"))
      (node (ref "IC1") (pin "6") (pinfunction "VCC_6") (pintype "power_in"))
      (node (ref "IC3") (pin "1") (pinfunction "VOUT_1") (pintype "output"))
      (node (ref "JP2") (pin "2") (pinfunction "2_2") (pintype "passive"))
      (node (ref "JP3A") (pin "2") (pinfunction "2_2") (pintype "passive"))
      (node (ref "PAD3") (pin "1") (pinfunction "P_1") (pintype "passive"))
      (node (ref "PAD4") (pin "1") (pinfunction "P_1") (pintype "passive"))
      (node (ref "R1") (pin "2") (pinfunction "2_2") (pintype "passive"))
    )
    (net (code "83") (name "_VCC") (class "Default")
      (node (ref "JP2T") (pin "2") (pinfunction "2_2") (pintype "passive"))
      (node (ref "P+5T") (pin "1") (pinfunction "P_1") (pintype "passive"))
    )
    (net (code "84") (name "unconnected-(IC1-PC4(ADC4{slash}SDA)-Pad27)") (class "Default")
      (node (ref "IC1") (pin "27") (pinfunction "PC4(ADC4/SDA)_27") (pintype "bidirectional"))
    )
    (net (code "85") (name "unconnected-(IC1-PC5(ADC5{slash}SCL)-Pad28)") (class "Default")
      (node (ref "IC1") (pin "28") (pinfunction "PC5(ADC5/SCL)_28") (pintype "bidirectional"))
    )
    (net (code "86") (name "unconnected-(JP2-Pad3)") (class "Default")
      (node (ref "JP2") (pin "3") (pinfunction "3_3") (pintype "passive"))
    )
    (net (code "87") (name "unconnected-(JP2-Pad4)") (class "Default")
      (node (ref "JP2") (pin "4") (pinfunction "4_4") (pintype "passive"))
    )
    (net (code "88") (name "unconnected-(JP2-Pad5)") (class "Default")
      (node (ref "JP2") (pin "5") (pinfunction "5_5") (pintype "passive"))
    )
    (net (code "89") (name "unconnected-(JP2-Pad6)") (class "Default")
      (node (ref "JP2") (pin "6") (pinfunction "6_6") (pintype "passive"))
    )
  )
)
